# schematic.net
KiCad netlist of a schematic drawn in EAGLE
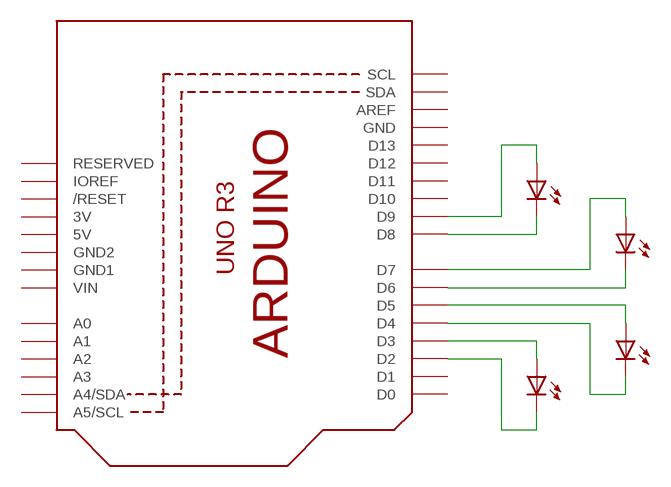
[diagram p0: schematic, sheet 1]

(export (version "E")
  (design (tool "Eeschema 10.0.6"))
  (components
    (comp (ref "LED2")
      (value "LED3MM")
      (footprint "eagle-import:LED3MM")
      (libsource (lib "eagle-import") (part "LED3MM"))
    )
    (comp (ref "LED3")
      (value "LED3MM")
      (footprint "eagle-import:LED3MM")
      (libsource (lib "eagle-import") (part "LED3MM"))
    )
    (comp (ref "LED4")
      (value "LED3MM")
      (footprint "eagle-import:LED3MM")
      (libsource (lib "eagle-import") (part "LED3MM"))
    )
    (comp (ref "LED5")
      (value "LED3MM")
      (footprint "eagle-import:LED3MM")
      (libsource (lib "eagle-import") (part "LED3MM"))
    )
    (comp (ref "U1")
      (value "ARDUINOR3-BPLACE")
      (footprint "eagle-import:ARDUINOR3-BPLACE")
      (libsource (lib "eagle-import") (part "ARDUINOR3-BPLACE"))
    )
  )
  (nets
    (net (code "1") (name "/3V") (class "Default")
      (node (ref "U1") (pin "3V") (pinfunction "3V_3V") (pintype "power_in"))
    )
    (net (code "2") (name "/5V") (class "Default")
      (node (ref "U1") (pin "5V") (pinfunction "5V_5V") (pintype "power_in"))
    )
    (net (code "3") (name "/GND") (class "Default")
      (node (ref "U1") (pin "GND") (pinfunction "GND_GND") (pintype "power_in"))
    )
    (net (code "4") (name "/GND1") (class "Default")
      (node (ref "U1") (pin "GND1") (pinfunction "GND1_GND1") (pintype "power_in"))
    )
    (net (code "5") (name "/GND2") (class "Default")
      (node (ref "U1") (pin "GND2") (pinfunction "GND2_GND2") (pintype "power_in"))
    )
    (net (code "6") (name "/VIN") (class "Default")
      (node (ref "U1") (pin "VIN") (pinfunction "VIN_VIN") (pintype "power_in"))
    )
    (net (code "7") (name "Net-(LED2-C)") (class "Default")
      (node (ref "LED2") (pin "K") (pinfunction "C_K") (pintype "passive"))
      (node (ref "U1") (pin "D2") (pinfunction "D2_D2") (pintype "bidirectional"))
    )
    (net (code "8") (name "Net-(LED2-PadA)") (class "Default")
      (node (ref "LED2") (pin "A") (pinfunction "A_A") (pintype "passive"))
      (node (ref "U1") (pin "D3") (pinfunction "D3_D3") (pintype "bidirectional"))
    )
    (net (code "9") (name "Net-(LED3-C)") (class "Default")
      (node (ref "LED3") (pin "K") (pinfunction "C_K") (pintype "passive"))
      (node (ref "U1") (pin "D4") (pinfunction "D4_D4") (pintype "bidirectional"))
    )
    (net (code "10") (name "Net-(LED3-PadA)") (class "Default")
      (node (ref "LED3") (pin "A") (pinfunction "A_A") (pintype "passive"))
      (node (ref "U1") (pin "D5") (pinfunction "D5_D5") (pintype "bidirectional"))
    )
    (net (code "11") (name "Net-(LED4-C)") (class "Default")
      (node (ref "LED4") (pin "K") (pinfunction "C_K") (pintype "passive"))
      (node (ref "U1") (pin "D8") (pinfunction "D8_D8") (pintype "bidirectional"))
    )
    (net (code "12") (name "Net-(LED4-PadA)") (class "Default")
      (node (ref "LED4") (pin "A") (pinfunction "A_A") (pintype "passive"))
      (node (ref "U1") (pin "D9") (pinfunction "D9_D9") (pintype "bidirectional"))
    )
    (net (code "13") (name "Net-(LED5-C)") (class "Default")
      (node (ref "LED5") (pin "K") (pinfunction "C_K") (pintype "passive"))
      (node (ref "U1") (pin "D6") (pinfunction "D6_D6") (pintype "bidirectional"))
    )
    (net (code "14") (name "Net-(LED5-PadA)") (class "Default")
      (node (ref "LED5") (pin "A") (pinfunction "A_A") (pintype "passive"))
      (node (ref "U1") (pin "D7") (pinfunction "D7_D7") (pintype "bidirectional"))
    )
    (net (code "15") (name "unconnected-(U1-A4{slash}SDA-PadA4)") (class "Default")
      (node (ref "U1") (pin "A4") (pinfunction "A4/SDA_A4") (pintype "bidirectional"))
    )
    (net (code "16") (name "unconnected-(U1-A5{slash}SCL-PadA5)") (class "Default")
      (node (ref "U1") (pin "A5") (pinfunction "A5/SCL_A5") (pintype "bidirectional"))
    )
    (net (code "17") (name "unconnected-(U1-PadA0)") (class "Default")
      (node (ref "U1") (pin "A0") (pinfunction "A0_A0") (pintype "bidirectional"))
    )
    (net (code "18") (name "unconnected-(U1-PadA1)") (class "Default")
      (node (ref "U1") (pin "A1") (pinfunction "A1_A1") (pintype "bidirectional"))
    )
    (net (code "19") (name "unconnected-(U1-PadA2)") (class "Default")
      (node (ref "U1") (pin "A2") (pinfunction "A2_A2") (pintype "bidirectional"))
    )
    (net (code "20") (name "unconnected-(U1-PadA3)") (class "Default")
      (node (ref "U1") (pin "A3") (pinfunction "A3_A3") (pintype "bidirectional"))
    )
    (net (code "21") (name "unconnected-(U1-PadAREF)") (class "Default")
      (node (ref "U1") (pin "AREF") (pinfunction "AREF_AREF") (pintype "bidirectional"))
    )
    (net (code "22") (name "unconnected-(U1-PadD0)") (class "Default")
      (node (ref "U1") (pin "D0") (pinfunction "D0_D0") (pintype "bidirectional"))
    )
    (net (code "23") (name "unconnected-(U1-PadD1)") (class "Default")
      (node (ref "U1") (pin "D1") (pinfunction "D1_D1") (pintype "bidirectional"))
    )
    (net (code "24") (name "unconnected-(U1-PadD10)") (class "Default")
      (node (ref "U1") (pin "D10") (pinfunction "D10_D10") (pintype "bidirectional"))
    )
    (net (code "25") (name "unconnected-(U1-PadD11)") (class "Default")
      (node (ref "U1") (pin "D11") (pinfunction "D11_D11") (pintype "bidirectional"))
    )
    (net (code "26") (name "unconnected-(U1-PadD12)") (class "Default")
      (node (ref "U1") (pin "D12") (pinfunction "D12_D12") (pintype "bidirectional"))
    )
    (net (code "27") (name "unconnected-(U1-PadD13)") (class "Default")
      (node (ref "U1") (pin "D13") (pinfunction "D13_D13") (pintype "bidirectional"))
    )
    (net (code "28") (name "unconnected-(U1-PadIOREF)") (class "Default")
      (node (ref "U1") (pin "IOREF") (pinfunction "IOREF_IOREF") (pintype "output"))
    )
    (net (code "29") (name "unconnected-(U1-PadRESERVED)") (class "Default")
      (node (ref "U1") (pin "RESERVED") (pinfunction "RESERVED_RESERVED") (pintype "no_connect"))
    )
    (net (code "30") (name "unconnected-(U1-PadSCL)") (class "Default")
      (node (ref "U1") (pin "SCL") (pinfunction "SCL_SCL") (pintype "bidirectional"))
    )
    (net (code "31") (name "unconnected-(U1-PadSDA)") (class "Default")
      (node (ref "U1") (pin "SDA") (pinfunction "SDA_SDA") (pintype "bidirectional"))
    )
    (net (code "32") (name "unconnected-(U1-{slash}RESET-PadRESET)") (class "Default")
      (node (ref "U1") (pin "RESET") (pinfunction "/RESET_RESET") (pintype "bidirectional"))
    )
  )
)
